# 2_Power.net
KiCad netlist of a schematic drawn in Altium Designer
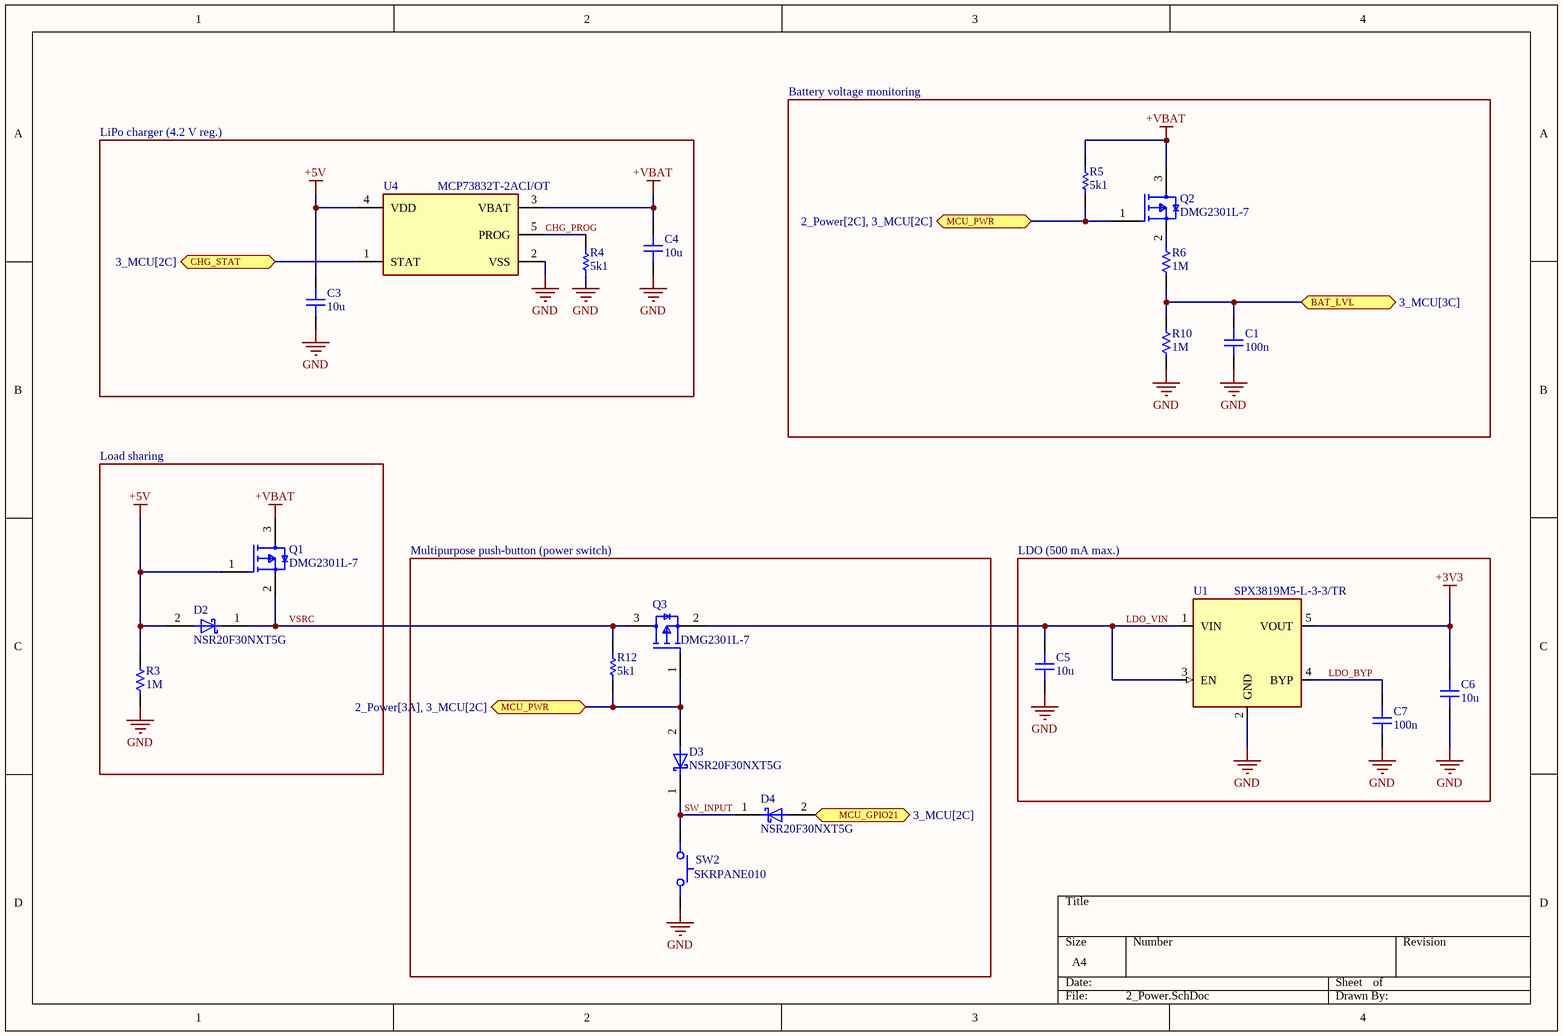
[diagram p0: 2_Power.SchDoc]

(export (version "E")
  (design (tool "Eeschema 10.0.6"))
  (components
    (comp (ref "C1")
      (value "100n")
      (footprint "CAP_0402")
      (description "Capacitor SMD 0402 16V")
      (libsource (lib "Schematic-Lib-PhilsLab") (part "CAP_0402_16V"))
    )
    (comp (ref "C3")
      (value "10u")
      (footprint "CAP_0402")
      (description "Capacitor SMD 0402 10V")
      (libsource (lib "Schematic-Lib-PhilsLab") (part "CAP_0402_10V"))
    )
    (comp (ref "C4")
      (value "10u")
      (footprint "CAP_0402")
      (description "Capacitor SMD 0402 10V")
      (libsource (lib "Schematic-Lib-PhilsLab") (part "CAP_0402_10V"))
    )
    (comp (ref "C5")
      (value "10u")
      (footprint "CAP_0402")
      (description "Capacitor SMD 0402 10V")
      (libsource (lib "Schematic-Lib-PhilsLab") (part "CAP_0402_10V"))
    )
    (comp (ref "C6")
      (value "10u")
      (footprint "CAP_0402")
      (description "Capacitor SMD 0402 10V")
      (libsource (lib "Schematic-Lib-PhilsLab") (part "CAP_0402_10V"))
    )
    (comp (ref "C7")
      (value "100n")
      (footprint "CAP_0402")
      (description "Capacitor SMD 0402 16V")
      (libsource (lib "Schematic-Lib-PhilsLab") (part "CAP_0402_16V"))
    )
    (comp (ref "D2")
      (value "NSR20F30NXT5G")
      (footprint "ONSC-DSN-2-512AB-01_V")
      (description "Rectifier Diode, Schottky, 1 Phase, 1 Element, 2A, 30V V(RRM), Silicon")
      (libsource (lib "Personal Workspace") (part "ONSC-D-K1A2-2"))
    )
    (comp (ref "D3")
      (value "NSR20F30NXT5G")
      (footprint "ONSC-DSN-2-512AB-01_V")
      (description "Rectifier Diode, Schottky, 1 Phase, 1 Element, 2A, 30V V(RRM), Silicon")
      (libsource (lib "Personal Workspace") (part "ONSC-D-K1A2-2"))
    )
    (comp (ref "D4")
      (value "NSR20F30NXT5G")
      (footprint "ONSC-DSN-2-512AB-01_V")
      (description "Rectifier Diode, Schottky, 1 Phase, 1 Element, 2A, 30V V(RRM), Silicon")
      (libsource (lib "Personal Workspace") (part "ONSC-D-K1A2-2"))
    )
    (comp (ref "Q1")
      (value "DMG2301L-7")
      (footprint "FP-SOT23-MFG")
      (description "MOSFET P-CH 20V 3A SOT23")
      (fields
        (field (name "MANUFACTURER") "Diodes Inc.")
        (field (name "OCTOPART") "https://octopart.com/dmg2301l-7-diodes+inc.-67250456")
      )
      (libsource (lib "Altium Content Vault") (part "b8f99f9e586195791e7fb11725ebaeb"))
    )
    (comp (ref "Q2")
      (value "DMG2301L-7")
      (footprint "FP-SOT23-MFG")
      (description "MOSFET P-CH 20V 3A SOT23")
      (fields
        (field (name "MANUFACTURER") "Diodes Inc.")
        (field (name "OCTOPART") "https://octopart.com/dmg2301l-7-diodes+inc.-67250456")
      )
      (libsource (lib "Altium Content Vault") (part "b8f99f9e586195791e7fb11725ebaeb"))
    )
    (comp (ref "Q3")
      (value "DMG2301L-7")
      (footprint "FP-SOT23-MFG")
      (description "MOSFET P-CH 20V 3A SOT23")
      (fields
        (field (name "MANUFACTURER") "Diodes Inc.")
        (field (name "OCTOPART") "https://octopart.com/dmg2301l-7-diodes+inc.-67250456")
      )
      (libsource (lib "Altium Content Vault") (part "b8f99f9e586195791e7fb11725ebaeb"))
    )
    (comp (ref "R3")
      (value "1M")
      (footprint "RES_0402")
      (description "Resistor SMD 0402")
      (libsource (lib "Schematic-Lib-PhilsLab") (part "RES_0402"))
    )
    (comp (ref "R4")
      (value "5k1")
      (footprint "RESC1005X40X25ML10T10")
      (fields (field (name "PART NUMBER") "RK73B1ETTP512J") (field (name "MANUFACTURER") "KOA Speer"))
      (libsource (lib "Altium Content Vault") (part "RES"))
    )
    (comp (ref "R5")
      (value "5k1")
      (footprint "RESC1005X40X25ML10T10")
      (fields (field (name "PART NUMBER") "RK73B1ETTP512J") (field (name "MANUFACTURER") "KOA Speer"))
      (libsource (lib "Altium Content Vault") (part "RES"))
    )
    (comp (ref "R6")
      (value "1M")
      (footprint "RES_0402")
      (description "Resistor SMD 0402")
      (libsource (lib "Schematic-Lib-PhilsLab") (part "RES_0402"))
    )
    (comp (ref "R10")
      (value "1M")
      (footprint "RES_0402")
      (description "Resistor SMD 0402")
      (libsource (lib "Schematic-Lib-PhilsLab") (part "RES_0402"))
    )
    (comp (ref "R12")
      (value "5k1")
      (footprint "RESC1005X40X25ML10T10")
      (fields (field (name "PART NUMBER") "RK73B1ETTP512J") (field (name "MANUFACTURER") "KOA Speer"))
      (libsource (lib "Altium Content Vault") (part "RES"))
    )
    (comp (ref "SW2")
      (value "SKRPANE010")
      (footprint "SKRPANE010")
      (description "Tactile Switch SMD SPST")
      (fields (field (name "MANUFACTURER") "Alps Alpine"))
      (libsource (lib "Schematic-Lib-PhilsLab") (part "SKRPANE010"))
    )
    (comp (ref "U1")
      (value "SPX3819M5-L-3-3/TR")
      (footprint "SOT-23-5")
      (description "500mA +3.3V Low-Noise LDO Voltage Regulator")
      (fields (field (name "MANUFACTURER") "MaxLinear"))
      (libsource (lib "Schematic-Lib-PhilsLab") (part "SPX3819M5-L-3-3/TR"))
    )
    (comp (ref "U4")
      (value "MCP73832T-2ACI/OT")
      (footprint "FP-C04-091-OT-MFG")
      (description "IC LI-ION/LI-POLY CTRLR SOT23-5")
      (libsource (lib "Altium Content Vault") (part "61f5a3bb3429d9e0caadea342aa3b19"))
    )
  )
  (nets
    (net (code "1") (name "+3V3") (class "Default")
      (node (ref "C6") (pin "2") (pinfunction "2_2") (pintype "passive"))
      (node (ref "U1") (pin "5") (pinfunction "VOUT_5") (pintype "power_in"))
    )
    (net (code "2") (name "+5V") (class "Default")
      (node (ref "C3") (pin "2") (pinfunction "2_2") (pintype "passive"))
      (node (ref "D2") (pin "2") (pinfunction "A_2") (pintype "passive"))
      (node (ref "Q1") (pin "1") (pinfunction "G_1") (pintype "passive"))
      (node (ref "R3") (pin "2") (pinfunction "2_2") (pintype "passive"))
      (node (ref "U4") (pin "4") (pinfunction "VDD_4") (pintype "power_in"))
    )
    (net (code "3") (name "+VBAT") (class "Default")
      (node (ref "C4") (pin "2") (pinfunction "2_2") (pintype "passive"))
      (node (ref "Q1") (pin "3") (pinfunction "D_3") (pintype "passive"))
      (node (ref "Q2") (pin "3") (pinfunction "D_3") (pintype "passive"))
      (node (ref "R5") (pin "2") (pinfunction "2_2") (pintype "passive"))
      (node (ref "U4") (pin "3") (pinfunction "VBAT_3") (pintype "power_in"))
    )
    (net (code "4") (name "/BAT_LVL") (class "Default")
      (node (ref "C1") (pin "2") (pinfunction "2_2") (pintype "passive"))
      (node (ref "R10") (pin "2") (pinfunction "2_2") (pintype "passive"))
      (node (ref "R6") (pin "1") (pinfunction "1_1") (pintype "passive"))
    )
    (net (code "5") (name "/CHG_PROG") (class "Default")
      (node (ref "R4") (pin "2") (pinfunction "2_2") (pintype "passive"))
      (node (ref "U4") (pin "5") (pinfunction "PROG_5") (pintype "passive"))
    )
    (net (code "6") (name "/CHG_STAT") (class "Default")
      (node (ref "U4") (pin "1") (pinfunction "STAT_1") (pintype "passive"))
    )
    (net (code "7") (name "/LDO_BYP") (class "Default")
      (node (ref "C7") (pin "2") (pinfunction "2_2") (pintype "passive"))
      (node (ref "U1") (pin "4") (pinfunction "BYP_4") (pintype "passive"))
    )
    (net (code "8") (name "/LDO_VIN") (class "Default")
      (node (ref "C5") (pin "2") (pinfunction "2_2") (pintype "passive"))
      (node (ref "Q3") (pin "2") (pinfunction "S_2") (pintype "passive"))
      (node (ref "U1") (pin "1") (pinfunction "VIN_1") (pintype "power_in"))
      (node (ref "U1") (pin "3") (pinfunction "EN_3") (pintype "input"))
    )
    (net (code "9") (name "/MCU_GPIO21") (class "Default")
      (node (ref "D4") (pin "2") (pinfunction "A_2") (pintype "passive"))
    )
    (net (code "10") (name "/MCU_PWR") (class "Default")
      (node (ref "D3") (pin "2") (pinfunction "A_2") (pintype "passive"))
      (node (ref "Q2") (pin "1") (pinfunction "G_1") (pintype "passive"))
      (node (ref "Q3") (pin "1") (pinfunction "G_1") (pintype "passive"))
      (node (ref "R12") (pin "1") (pinfunction "1_1") (pintype "passive"))
      (node (ref "R5") (pin "1") (pinfunction "1_1") (pintype "passive"))
    )
    (net (code "11") (name "/SW_INPUT") (class "Default")
      (node (ref "D3") (pin "1") (pinfunction "K_1") (pintype "passive"))
      (node (ref "D4") (pin "1") (pinfunction "K_1") (pintype "passive"))
      (node (ref "SW2") (pin "34") (pintype "passive"))
    )
    (net (code "12") (name "/VSRC") (class "Default")
      (node (ref "D2") (pin "1") (pinfunction "K_1") (pintype "passive"))
      (node (ref "Q1") (pin "2") (pinfunction "S_2") (pintype "passive"))
      (node (ref "Q3") (pin "3") (pinfunction "D_3") (pintype "passive"))
      (node (ref "R12") (pin "2") (pinfunction "2_2") (pintype "passive"))
    )
    (net (code "13") (name "GND") (class "Default")
      (node (ref "C1") (pin "1") (pinfunction "1_1") (pintype "passive"))
      (node (ref "C3") (pin "1") (pinfunction "1_1") (pintype "passive"))
      (node (ref "C4") (pin "1") (pinfunction "1_1") (pintype "passive"))
      (node (ref "C5") (pin "1") (pinfunction "1_1") (pintype "passive"))
      (node (ref "C6") (pin "1") (pinfunction "1_1") (pintype "passive"))
      (node (ref "C7") (pin "1") (pinfunction "1_1") (pintype "passive"))
      (node (ref "R10") (pin "1") (pinfunction "1_1") (pintype "passive"))
      (node (ref "R3") (pin "1") (pinfunction "1_1") (pintype "passive"))
      (node (ref "R4") (pin "1") (pinfunction "1_1") (pintype "passive"))
      (node (ref "SW2") (pin "12") (pintype "passive"))
      (node (ref "U1") (pin "2") (pinfunction "GND_2") (pintype "power_in"))
      (node (ref "U4") (pin "2") (pinfunction "VSS_2") (pintype "power_in"))
    )
    (net (code "14") (name "Net-(Q2-S)") (class "Default")
      (node (ref "Q2") (pin "2") (pinfunction "S_2") (pintype "passive"))
      (node (ref "R6") (pin "2") (pinfunction "2_2") (pintype "passive"))
    )
  )
)
